# Aeroponics_Control.net
KiCad netlist of a schematic drawn in EAGLE
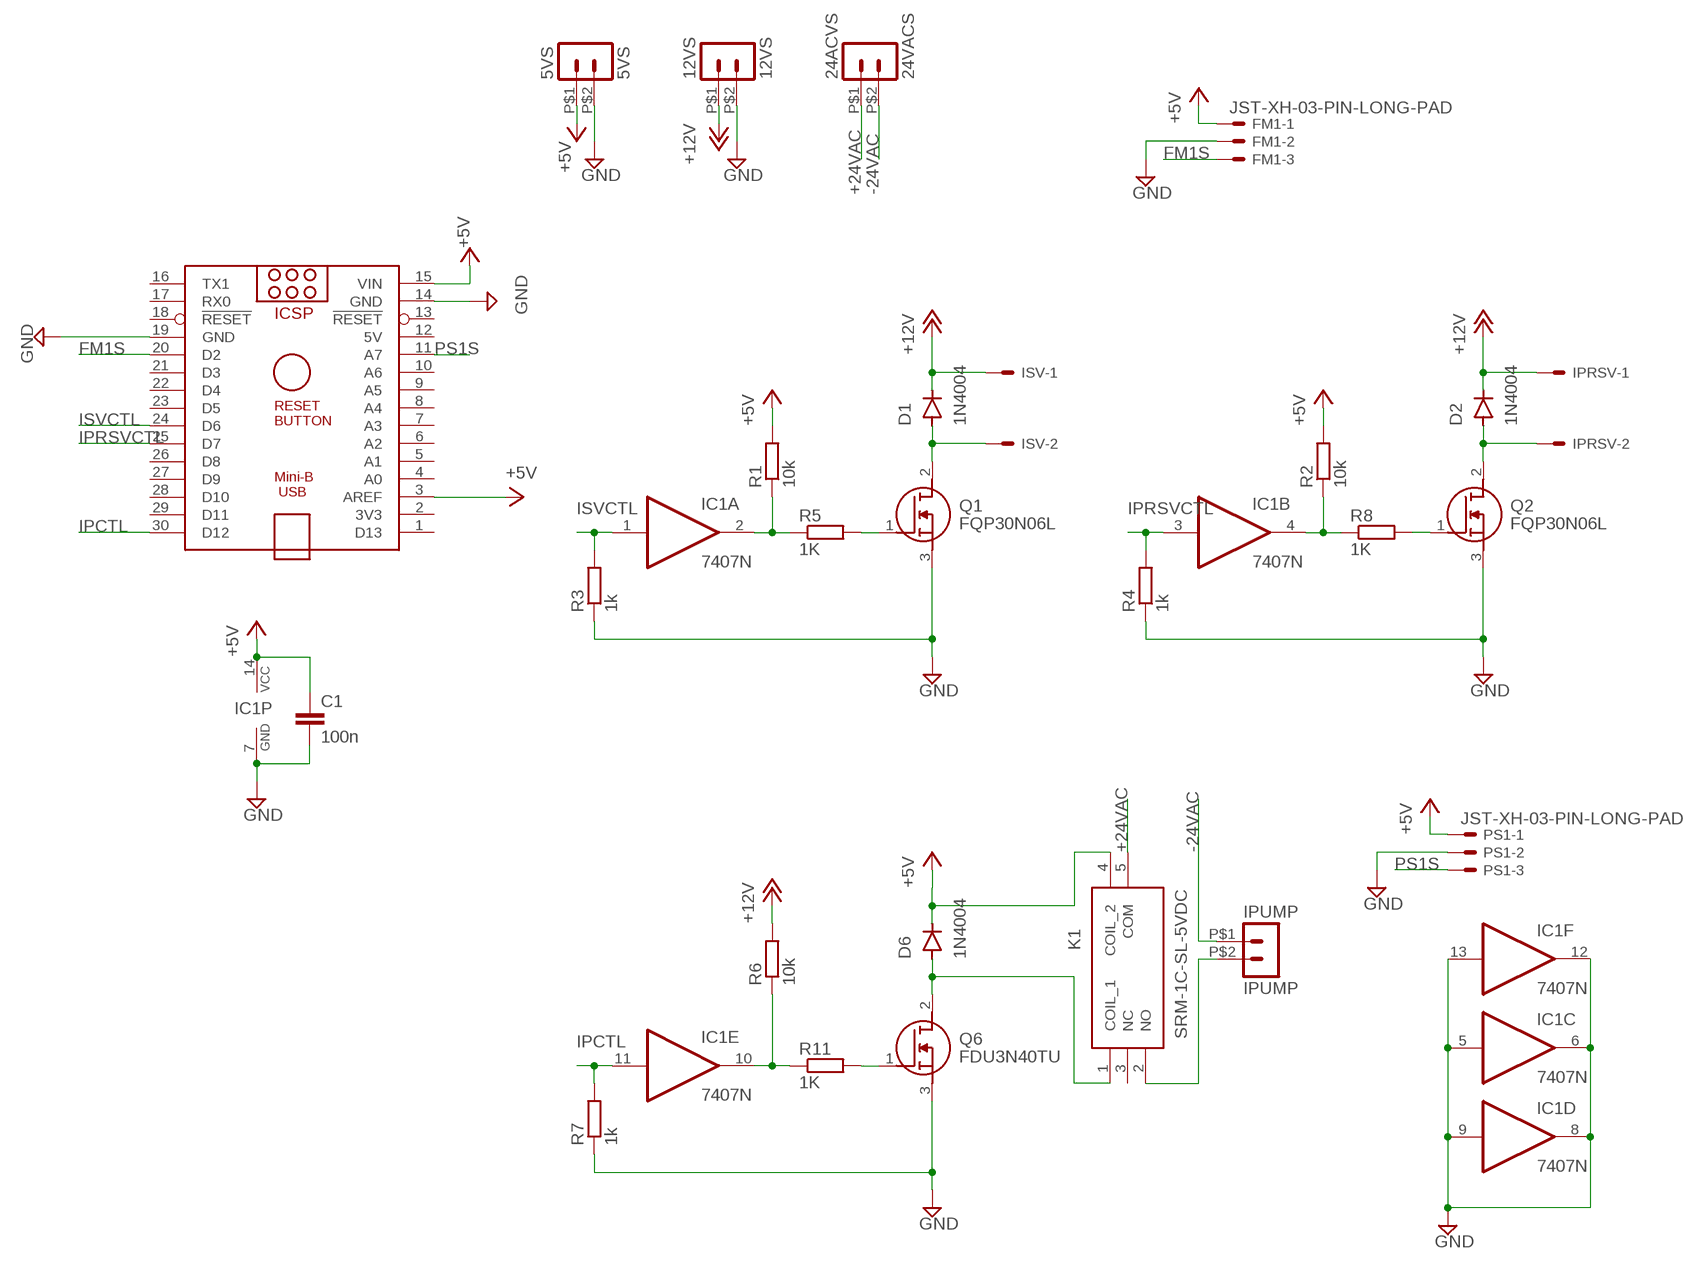
[diagram p0: schematic, sheet 1]

(export (version "E")
  (design (tool "Eeschema 10.0.6"))
  (components
    (comp (ref "5VS")
      (value "5VS")
      (footprint "eagle-import:43650-0215")
      (libsource (lib "eagle-import") (part "HEADER_POS2_?43650-0215"))
    )
    (comp (ref "12VS")
      (value "12VS")
      (footprint "eagle-import:43650-0215")
      (libsource (lib "eagle-import") (part "HEADER_POS2_?43650-0215"))
    )
    (comp (ref "24ACVS")
      (value "24VACS")
      (footprint "eagle-import:43650-0215")
      (libsource (lib "eagle-import") (part "HEADER_POS2_?43650-0215"))
    )
    (comp (ref "C1")
      (value "100n")
      (footprint "eagle-import:C050-024X044")
      (libsource (lib "eagle-import") (part "C-EU050-024X044"))
    )
    (comp (ref "D1")
      (value "1N4004")
      (footprint "eagle-import:DO-41")
      (fields
        (field (name "DIGIKEY_PART_NUMBER") "1N4004MSCT-ND")
        (field (name "MANUFACTURER") "Micro Commercial Co")
        (field (name "CREATED_BY") "PCBLayout.com")
      )
      (libsource (lib "eagle-import") (part "1N4004"))
    )
    (comp (ref "D2")
      (value "1N4004")
      (footprint "eagle-import:DO-41")
      (fields
        (field (name "DIGIKEY_PART_NUMBER") "1N4004MSCT-ND")
        (field (name "MANUFACTURER") "Micro Commercial Co")
        (field (name "CREATED_BY") "PCBLayout.com")
      )
      (libsource (lib "eagle-import") (part "1N4004"))
    )
    (comp (ref "D6")
      (value "1N4004")
      (footprint "eagle-import:DO-41")
      (fields
        (field (name "DIGIKEY_PART_NUMBER") "1N4004MSCT-ND")
        (field (name "MANUFACTURER") "Micro Commercial Co")
        (field (name "CREATED_BY") "PCBLayout.com")
      )
      (libsource (lib "eagle-import") (part "1N4004"))
    )
    (comp (ref "FM1")
      (value "JST-XH-03-PIN-LONG-PAD")
      (footprint "eagle-import:JST-XH-03-PACKAGE-LONG-PAD")
      (libsource (lib "eagle-import") (part "JST-XH-03-PIN-LONG-PAD"))
    )
    (comp (ref "IC1")
      (value "7407N")
      (footprint "eagle-import:DIL14")
      (libsource (lib "eagle-import") (part "7407N"))
    )
    (comp (ref "IPRSV")
      (value "JST-XH-02-PIN-LONG-PAD")
      (footprint "eagle-import:JST-XH-02-PACKAGE-LONG-PAD")
      (libsource (lib "eagle-import") (part "JST-XH-02-PIN-LONG-PAD"))
    )
    (comp (ref "IPUMP")
      (value "IPUMP")
      (footprint "eagle-import:43650-0215")
      (libsource (lib "eagle-import") (part "HEADER_POS2_?43650-0215"))
    )
    (comp (ref "ISV")
      (value "JST-XH-02-PIN-LONG-PAD")
      (footprint "eagle-import:JST-XH-02-PACKAGE-LONG-PAD")
      (libsource (lib "eagle-import") (part "JST-XH-02-PIN-LONG-PAD"))
    )
    (comp (ref "K1")
      (value "SRM-1C-SL-5VDC")
      (footprint "eagle-import:SRM1CSL5VDC")
      (libsource (lib "eagle-import") (part "SRM-1C-SL-5VDC"))
    )
    (comp (ref "PCB1")
      (value "ARDUINO_NANOARDUINO_NANO_HEADERS")
      (footprint "eagle-import:ARDUINO_NANO")
      (libsource (lib "eagle-import") (part "ARDUINO_NANO"))
    )
    (comp (ref "PS1")
      (value "JST-XH-03-PIN-LONG-PAD")
      (footprint "eagle-import:JST-XH-03-PACKAGE-LONG-PAD")
      (libsource (lib "eagle-import") (part "JST-XH-03-PIN-LONG-PAD"))
    )
    (comp (ref "Q1")
      (value "FQP30N06L")
      (footprint "eagle-import:TO254P470X1016X2019-3P")
      (fields (field (name "RS_PART_NUMBER") "8075863P"))
      (libsource (lib "eagle-import") (part "FQP30N06L"))
    )
    (comp (ref "Q2")
      (value "FQP30N06L")
      (footprint "eagle-import:TO254P470X1016X2019-3P")
      (fields (field (name "RS_PART_NUMBER") "8075863P"))
      (libsource (lib "eagle-import") (part "FQP30N06L"))
    )
    (comp (ref "Q6")
      (value "FDU3N40TU")
      (footprint "eagle-import:TO229P250X658X985-3P")
      (fields (field (name "RS_PART_NUMBER") "8070701P"))
      (libsource (lib "eagle-import") (part "FDU3N40TU"))
    )
    (comp (ref "R1")
      (value "10k")
      (footprint "eagle-import:0204_7")
      (libsource (lib "eagle-import") (part "R-EU_0204/7"))
    )
    (comp (ref "R2")
      (value "10k")
      (footprint "eagle-import:0204_7")
      (libsource (lib "eagle-import") (part "R-EU_0204/7"))
    )
    (comp (ref "R3")
      (value "1k")
      (footprint "eagle-import:0204_7")
      (libsource (lib "eagle-import") (part "R-EU_0204/7"))
    )
    (comp (ref "R4")
      (value "1k")
      (footprint "eagle-import:0204_7")
      (libsource (lib "eagle-import") (part "R-EU_0204/7"))
    )
    (comp (ref "R5")
      (value "1K")
      (footprint "eagle-import:0204_7")
      (libsource (lib "eagle-import") (part "R-EU_0204/7"))
    )
    (comp (ref "R6")
      (value "10k")
      (footprint "eagle-import:0204_7")
      (libsource (lib "eagle-import") (part "R-EU_0204/7"))
    )
    (comp (ref "R7")
      (value "1k")
      (footprint "eagle-import:0204_7")
      (libsource (lib "eagle-import") (part "R-EU_0204/7"))
    )
    (comp (ref "R8")
      (value "1K")
      (footprint "eagle-import:0204_7")
      (libsource (lib "eagle-import") (part "R-EU_0204/7"))
    )
    (comp (ref "R11")
      (value "1K")
      (footprint "eagle-import:0204_7")
      (libsource (lib "eagle-import") (part "R-EU_0204/7"))
    )
  )
  (nets
    (net (code "1") (name "+5V") (class "Default")
      (node (ref "5VS") (pin "P$1") (pinfunction "1_P$1") (pintype "passive"))
      (node (ref "C1") (pin "1") (pinfunction "1_1") (pintype "passive"))
      (node (ref "D6") (pin "C") (pinfunction "C_C") (pintype "passive"))
      (node (ref "FM1") (pin "1") (pinfunction "S_1") (pintype "passive"))
      (node (ref "IC1") (pin "14") (pinfunction "VCC_14") (pintype "power_in"))
      (node (ref "K1") (pin "4") (pinfunction "COIL_2_4") (pintype "bidirectional"))
      (node (ref "PCB1") (pin "15") (pinfunction "VIN_15") (pintype "power_in"))
      (node (ref "PCB1") (pin "3") (pinfunction "AREF_3") (pintype "input"))
      (node (ref "PS1") (pin "1") (pinfunction "S_1") (pintype "passive"))
      (node (ref "R1") (pin "2") (pinfunction "2_2") (pintype "passive"))
      (node (ref "R2") (pin "2") (pinfunction "2_2") (pintype "passive"))
    )
    (net (code "2") (name "+12V") (class "Default")
      (node (ref "12VS") (pin "P$1") (pinfunction "1_P$1") (pintype "passive"))
      (node (ref "D1") (pin "C") (pinfunction "C_C") (pintype "passive"))
      (node (ref "D2") (pin "C") (pinfunction "C_C") (pintype "passive"))
      (node (ref "IPRSV") (pin "1") (pinfunction "S_1") (pintype "passive"))
      (node (ref "ISV") (pin "1") (pinfunction "S_1") (pintype "passive"))
      (node (ref "R6") (pin "2") (pinfunction "2_2") (pintype "passive"))
    )
    (net (code "3") (name "/+24VAC") (class "Default")
      (node (ref "24ACVS") (pin "P$1") (pinfunction "1_P$1") (pintype "passive"))
      (node (ref "K1") (pin "5") (pinfunction "COM_5") (pintype "bidirectional"))
    )
    (net (code "4") (name "/-24VAC") (class "Default")
      (node (ref "24ACVS") (pin "P$2") (pinfunction "2_P$2") (pintype "passive"))
      (node (ref "IPUMP") (pin "P$1") (pinfunction "1_P$1") (pintype "passive"))
    )
    (net (code "5") (name "/5V") (class "Default")
      (node (ref "PCB1") (pin "12") (pinfunction "5V_12") (pintype "power_in"))
    )
    (net (code "6") (name "/FM1S") (class "Default")
      (node (ref "FM1") (pin "3") (pinfunction "S_3") (pintype "passive"))
      (node (ref "PCB1") (pin "20") (pinfunction "D2_20") (pintype "bidirectional"))
    )
    (net (code "7") (name "/IPCTL") (class "Default")
      (node (ref "IC1") (pin "11") (pinfunction "I_11") (pintype "input"))
      (node (ref "PCB1") (pin "30") (pinfunction "D12_30") (pintype "bidirectional"))
      (node (ref "R7") (pin "2") (pinfunction "2_2") (pintype "passive"))
    )
    (net (code "8") (name "/IPRSVCTL") (class "Default")
      (node (ref "IC1") (pin "3") (pinfunction "I_3") (pintype "input"))
      (node (ref "PCB1") (pin "25") (pinfunction "D7_25") (pintype "bidirectional"))
      (node (ref "R4") (pin "2") (pinfunction "2_2") (pintype "passive"))
    )
    (net (code "9") (name "/ISVCTL") (class "Default")
      (node (ref "IC1") (pin "1") (pinfunction "I_1") (pintype "input"))
      (node (ref "PCB1") (pin "24") (pinfunction "D6_24") (pintype "bidirectional"))
      (node (ref "R3") (pin "2") (pinfunction "2_2") (pintype "passive"))
    )
    (net (code "10") (name "/PS1S") (class "Default")
      (node (ref "PCB1") (pin "11") (pinfunction "A7_11") (pintype "bidirectional"))
      (node (ref "PS1") (pin "3") (pinfunction "S_3") (pintype "passive"))
    )
    (net (code "11") (name "GND") (class "Default")
      (node (ref "12VS") (pin "P$2") (pinfunction "2_P$2") (pintype "passive"))
      (node (ref "5VS") (pin "P$2") (pinfunction "2_P$2") (pintype "passive"))
      (node (ref "C1") (pin "2") (pinfunction "2_2") (pintype "passive"))
      (node (ref "FM1") (pin "2") (pinfunction "S_2") (pintype "passive"))
      (node (ref "IC1") (pin "12") (pinfunction "O_12") (pintype "open_collector"))
      (node (ref "IC1") (pin "13") (pinfunction "I_13") (pintype "input"))
      (node (ref "IC1") (pin "5") (pinfunction "I_5") (pintype "input"))
      (node (ref "IC1") (pin "6") (pinfunction "O_6") (pintype "open_collector"))
      (node (ref "IC1") (pin "7") (pinfunction "GND_7") (pintype "power_in"))
      (node (ref "IC1") (pin "8") (pinfunction "O_8") (pintype "open_collector"))
      (node (ref "IC1") (pin "9") (pinfunction "I_9") (pintype "input"))
      (node (ref "PCB1") (pin "14") (pinfunction "GND_14") (pintype "power_in"))
      (node (ref "PCB1") (pin "19") (pinfunction "GND_19") (pintype "power_in"))
      (node (ref "PS1") (pin "2") (pinfunction "S_2") (pintype "passive"))
      (node (ref "Q1") (pin "3") (pinfunction "S_3") (pintype "bidirectional"))
      (node (ref "Q2") (pin "3") (pinfunction "S_3") (pintype "bidirectional"))
      (node (ref "Q6") (pin "3") (pinfunction "S_3") (pintype "bidirectional"))
      (node (ref "R3") (pin "1") (pinfunction "1_1") (pintype "passive"))
      (node (ref "R4") (pin "1") (pinfunction "1_1") (pintype "passive"))
      (node (ref "R7") (pin "1") (pinfunction "1_1") (pintype "passive"))
    )
    (net (code "12") (name "Net-(IC1A-O)") (class "Default")
      (node (ref "IC1") (pin "2") (pinfunction "O_2") (pintype "open_collector"))
      (node (ref "R1") (pin "1") (pinfunction "1_1") (pintype "passive"))
      (node (ref "R5") (pin "1") (pinfunction "1_1") (pintype "passive"))
    )
    (net (code "13") (name "Net-(IC1B-O)") (class "Default")
      (node (ref "IC1") (pin "4") (pinfunction "O_4") (pintype "open_collector"))
      (node (ref "R2") (pin "1") (pinfunction "1_1") (pintype "passive"))
      (node (ref "R8") (pin "1") (pinfunction "1_1") (pintype "passive"))
    )
    (net (code "14") (name "Net-(IC1E-O)") (class "Default")
      (node (ref "IC1") (pin "10") (pinfunction "O_10") (pintype "open_collector"))
      (node (ref "R11") (pin "1") (pinfunction "1_1") (pintype "passive"))
      (node (ref "R6") (pin "1") (pinfunction "1_1") (pintype "passive"))
    )
    (net (code "15") (name "Net-(IPRSVB-S)") (class "Default")
      (node (ref "D2") (pin "A") (pinfunction "A_A") (pintype "passive"))
      (node (ref "IPRSV") (pin "2") (pinfunction "S_2") (pintype "passive"))
      (node (ref "Q2") (pin "2") (pinfunction "D_2") (pintype "bidirectional"))
    )
    (net (code "16") (name "Net-(IPUMP-2)") (class "Default")
      (node (ref "IPUMP") (pin "P$2") (pinfunction "2_P$2") (pintype "passive"))
      (node (ref "K1") (pin "2") (pinfunction "NO_2") (pintype "bidirectional"))
    )
    (net (code "17") (name "Net-(ISVB-S)") (class "Default")
      (node (ref "D1") (pin "A") (pinfunction "A_A") (pintype "passive"))
      (node (ref "ISV") (pin "2") (pinfunction "S_2") (pintype "passive"))
      (node (ref "Q1") (pin "2") (pinfunction "D_2") (pintype "bidirectional"))
    )
    (net (code "18") (name "Net-(K1-COIL_1)") (class "Default")
      (node (ref "D6") (pin "A") (pinfunction "A_A") (pintype "passive"))
      (node (ref "K1") (pin "1") (pinfunction "COIL_1_1") (pintype "bidirectional"))
      (node (ref "Q6") (pin "2") (pinfunction "D_2") (pintype "bidirectional"))
    )
    (net (code "19") (name "Net-(Q1-G)") (class "Default")
      (node (ref "Q1") (pin "1") (pinfunction "G_1") (pintype "bidirectional"))
      (node (ref "R5") (pin "2") (pinfunction "2_2") (pintype "passive"))
    )
    (net (code "20") (name "Net-(Q2-G)") (class "Default")
      (node (ref "Q2") (pin "1") (pinfunction "G_1") (pintype "bidirectional"))
      (node (ref "R8") (pin "2") (pinfunction "2_2") (pintype "passive"))
    )
    (net (code "21") (name "Net-(Q6-G)") (class "Default")
      (node (ref "Q6") (pin "1") (pinfunction "G_1") (pintype "bidirectional"))
      (node (ref "R11") (pin "2") (pinfunction "2_2") (pintype "passive"))
    )
    (net (code "22") (name "unconnected-(K1-NC-Pad3)") (class "Default")
      (node (ref "K1") (pin "3") (pinfunction "NC_3") (pintype "no_connect"))
    )
    (net (code "23") (name "unconnected-(PCB1-3V3-Pad2)") (class "Default")
      (node (ref "PCB1") (pin "2") (pinfunction "3V3_2") (pintype "output"))
    )
    (net (code "24") (name "unconnected-(PCB1-A0-Pad4)") (class "Default")
      (node (ref "PCB1") (pin "4") (pinfunction "A0_4") (pintype "bidirectional"))
    )
    (net (code "25") (name "unconnected-(PCB1-A1-Pad5)") (class "Default")
      (node (ref "PCB1") (pin "5") (pinfunction "A1_5") (pintype "bidirectional"))
    )
    (net (code "26") (name "unconnected-(PCB1-A2-Pad6)") (class "Default")
      (node (ref "PCB1") (pin "6") (pinfunction "A2_6") (pintype "bidirectional"))
    )
    (net (code "27") (name "unconnected-(PCB1-A3-Pad7)") (class "Default")
      (node (ref "PCB1") (pin "7") (pinfunction "A3_7") (pintype "bidirectional"))
    )
    (net (code "28") (name "unconnected-(PCB1-A4-Pad8)") (class "Default")
      (node (ref "PCB1") (pin "8") (pinfunction "A4_8") (pintype "bidirectional"))
    )
    (net (code "29") (name "unconnected-(PCB1-A5-Pad9)") (class "Default")
      (node (ref "PCB1") (pin "9") (pinfunction "A5_9") (pintype "bidirectional"))
    )
    (net (code "30") (name "unconnected-(PCB1-A6-Pad10)") (class "Default")
      (node (ref "PCB1") (pin "10") (pinfunction "A6_10") (pintype "bidirectional"))
    )
    (net (code "31") (name "unconnected-(PCB1-D3-Pad21)") (class "Default")
      (node (ref "PCB1") (pin "21") (pinfunction "D3_21") (pintype "bidirectional"))
    )
    (net (code "32") (name "unconnected-(PCB1-D4-Pad22)") (class "Default")
      (node (ref "PCB1") (pin "22") (pinfunction "D4_22") (pintype "bidirectional"))
    )
    (net (code "33") (name "unconnected-(PCB1-D5-Pad23)") (class "Default")
      (node (ref "PCB1") (pin "23") (pinfunction "D5_23") (pintype "bidirectional"))
    )
    (net (code "34") (name "unconnected-(PCB1-D8-Pad26)") (class "Default")
      (node (ref "PCB1") (pin "26") (pinfunction "D8_26") (pintype "bidirectional"))
    )
    (net (code "35") (name "unconnected-(PCB1-D9-Pad27)") (class "Default")
      (node (ref "PCB1") (pin "27") (pinfunction "D9_27") (pintype "bidirectional"))
    )
    (net (code "36") (name "unconnected-(PCB1-D10-Pad28)") (class "Default")
      (node (ref "PCB1") (pin "28") (pinfunction "D10_28") (pintype "bidirectional"))
    )
    (net (code "37") (name "unconnected-(PCB1-D11-Pad29)") (class "Default")
      (node (ref "PCB1") (pin "29") (pinfunction "D11_29") (pintype "bidirectional"))
    )
    (net (code "38") (name "unconnected-(PCB1-D13-Pad1)") (class "Default")
      (node (ref "PCB1") (pin "1") (pinfunction "D13_1") (pintype "bidirectional"))
    )
    (net (code "39") (name "unconnected-(PCB1-RX0-Pad17)") (class "Default")
      (node (ref "PCB1") (pin "17") (pinfunction "RX0_17") (pintype "bidirectional"))
    )
    (net (code "40") (name "unconnected-(PCB1-TX1-Pad16)") (class "Default")
      (node (ref "PCB1") (pin "16") (pinfunction "TX1_16") (pintype "bidirectional"))
    )
    (net (code "41") (name "unconnected-(PCB1-~{RESET}-Pad13)") (class "Default")
      (node (ref "PCB1") (pin "13") (pinfunction "~{RESET}_13") (pintype "input"))
    )
    (net (code "42") (name "unconnected-(PCB1-~{RESET}-Pad18)") (class "Default")
      (node (ref "PCB1") (pin "18") (pinfunction "~{RESET}_18") (pintype "input"))
    )
  )
)
